# 12_SAVEFLAGS.net
KiCad netlist of a schematic drawn in EAGLE
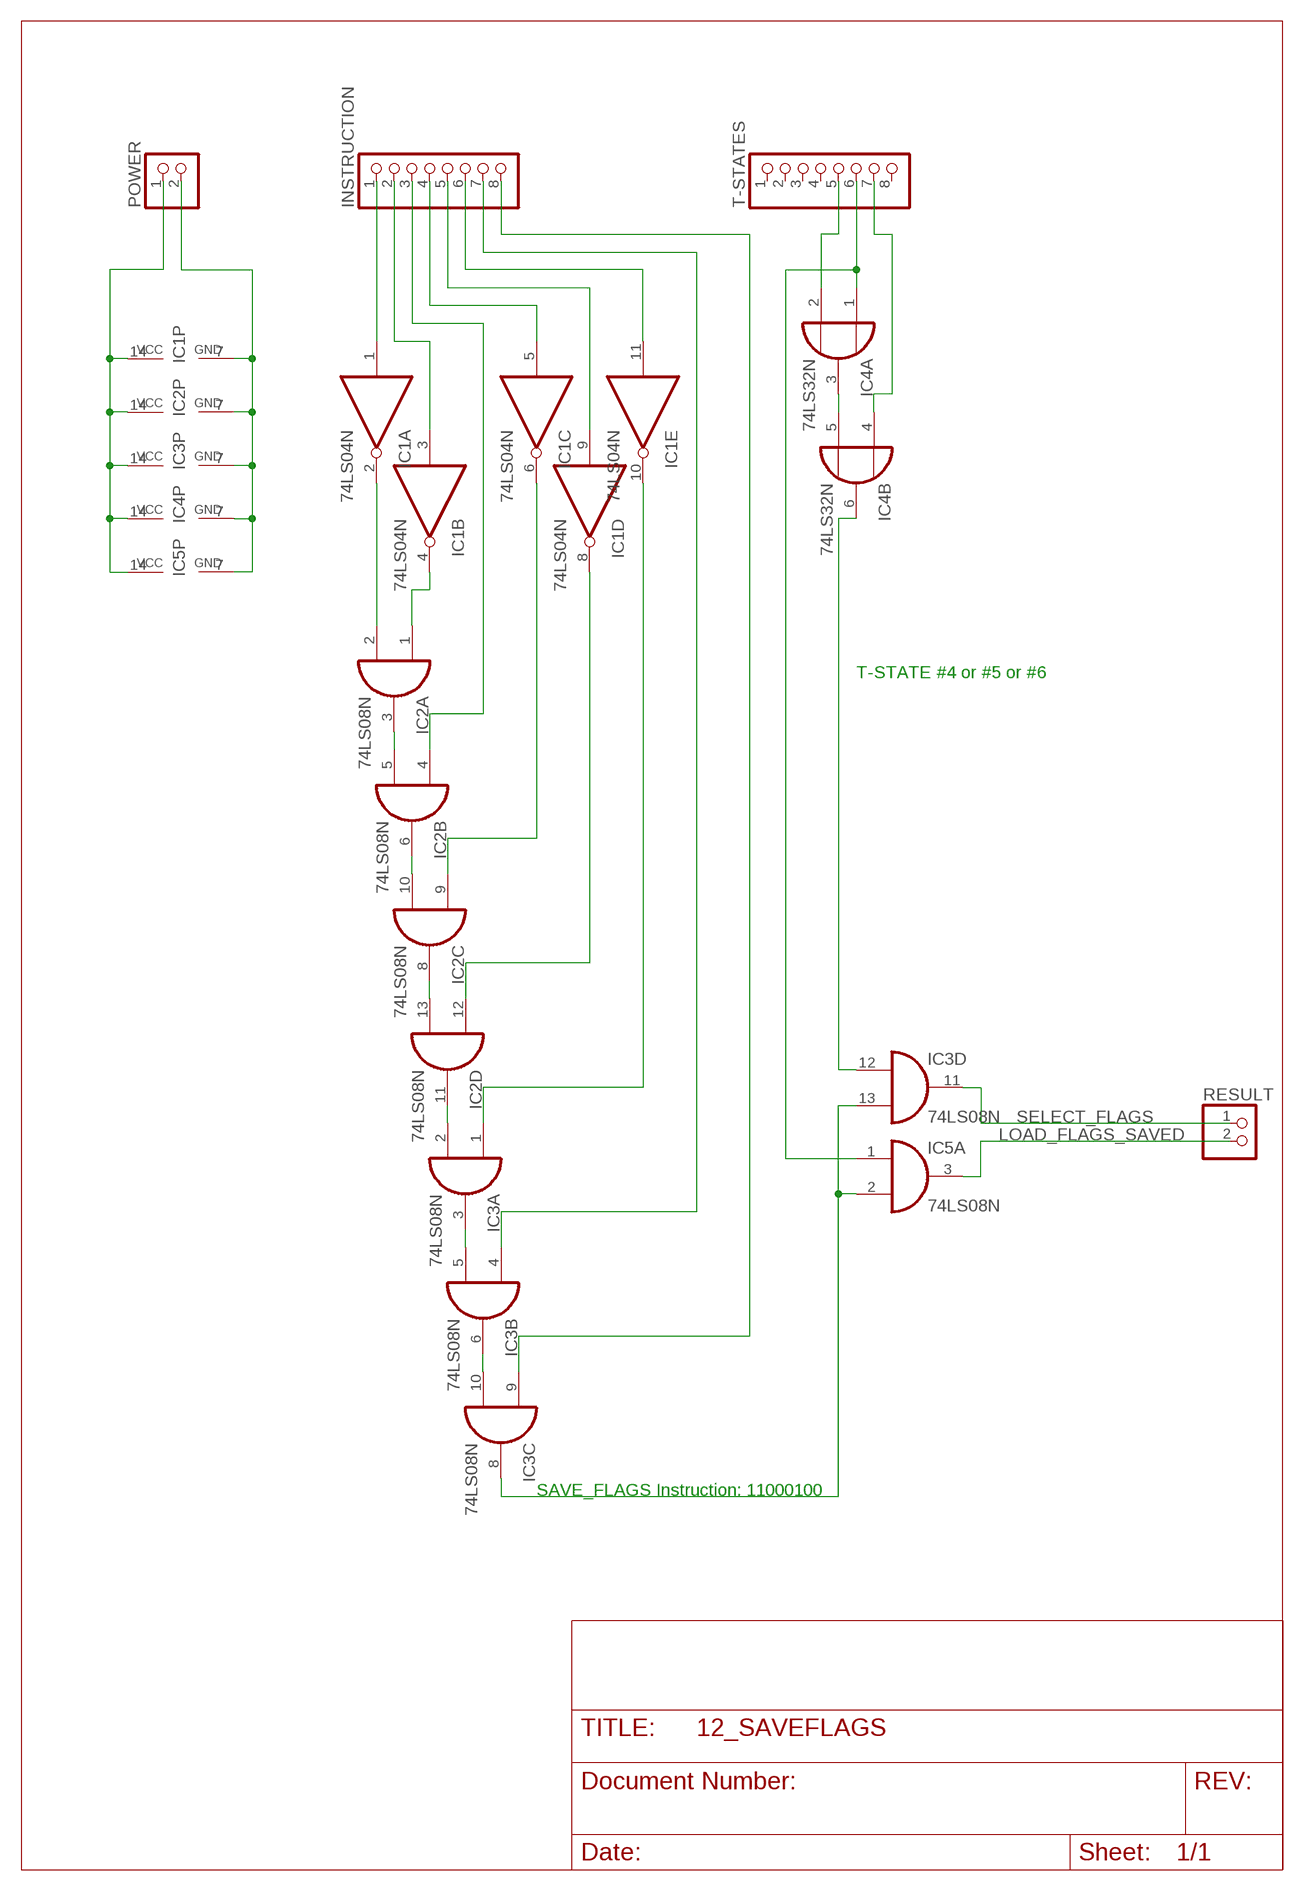
[diagram p0: schematic, sheet 1]

(export (version "E")
  (design (tool "Eeschema 10.0.6"))
  (components
    (comp (ref "IC1")
      (value "74LS04N")
      (footprint "eagle-import:DIL14")
      (libsource (lib "eagle-import") (part "7404NLS"))
    )
    (comp (ref "IC2")
      (value "74LS08N")
      (footprint "eagle-import:DIL14")
      (libsource (lib "eagle-import") (part "7408NLS"))
    )
    (comp (ref "IC3")
      (value "74LS08N")
      (footprint "eagle-import:DIL14")
      (libsource (lib "eagle-import") (part "7408NLS"))
    )
    (comp (ref "IC4")
      (value "74LS32N")
      (footprint "eagle-import:DIL14")
      (libsource (lib "eagle-import") (part "7432NLS"))
    )
    (comp (ref "IC5")
      (value "74LS08N")
      (footprint "eagle-import:DIL14")
      (libsource (lib "eagle-import") (part "7408NLS"))
    )
    (comp (ref "INSTRUCTION")
      (value "PINHD-1X8")
      (footprint "eagle-import:1X08")
      (libsource (lib "eagle-import") (part "PINHD-1X8"))
    )
    (comp (ref "POWER")
      (value "PINHD-1X2")
      (footprint "eagle-import:1X02")
      (libsource (lib "eagle-import") (part "PINHD-1X2"))
    )
    (comp (ref "RESULT")
      (value "PINHD-1X2")
      (footprint "eagle-import:1X02")
      (libsource (lib "eagle-import") (part "PINHD-1X2"))
    )
    (comp (ref "T-STATES")
      (value "PINHD-1X8")
      (footprint "eagle-import:1X08")
      (libsource (lib "eagle-import") (part "PINHD-1X8"))
    )
  )
  (nets
    (net (code "1") (name "/LOAD_FLAGS_SAVED") (class "Default")
      (node (ref "IC5") (pin "3") (pinfunction "O_3") (pintype "output"))
      (node (ref "RESULT") (pin "2") (pinfunction "2_2") (pintype "passive"))
    )
    (net (code "2") (name "/SELECT_FLAGS") (class "Default")
      (node (ref "IC3") (pin "11") (pinfunction "O_11") (pintype "output"))
      (node (ref "RESULT") (pin "1") (pinfunction "1_1") (pintype "passive"))
    )
    (net (code "3") (name "Net-(IC1A-I)") (class "Default")
      (node (ref "IC1") (pin "1") (pinfunction "I_1") (pintype "input"))
      (node (ref "INSTRUCTION") (pin "1") (pinfunction "1_1") (pintype "passive"))
    )
    (net (code "4") (name "Net-(IC1A-O)") (class "Default")
      (node (ref "IC1") (pin "2") (pinfunction "O_2") (pintype "output"))
      (node (ref "IC2") (pin "2") (pinfunction "I1_2") (pintype "input"))
    )
    (net (code "5") (name "Net-(IC1B-I)") (class "Default")
      (node (ref "IC1") (pin "3") (pinfunction "I_3") (pintype "input"))
      (node (ref "INSTRUCTION") (pin "2") (pinfunction "2_2") (pintype "passive"))
    )
    (net (code "6") (name "Net-(IC1B-O)") (class "Default")
      (node (ref "IC1") (pin "4") (pinfunction "O_4") (pintype "output"))
      (node (ref "IC2") (pin "1") (pinfunction "I0_1") (pintype "input"))
    )
    (net (code "7") (name "Net-(IC1C-I)") (class "Default")
      (node (ref "IC1") (pin "5") (pinfunction "I_5") (pintype "input"))
      (node (ref "INSTRUCTION") (pin "4") (pinfunction "4_4") (pintype "passive"))
    )
    (net (code "8") (name "Net-(IC1C-O)") (class "Default")
      (node (ref "IC1") (pin "6") (pinfunction "O_6") (pintype "output"))
      (node (ref "IC2") (pin "9") (pinfunction "I0_9") (pintype "input"))
    )
    (net (code "9") (name "Net-(IC1D-I)") (class "Default")
      (node (ref "IC1") (pin "9") (pinfunction "I_9") (pintype "input"))
      (node (ref "INSTRUCTION") (pin "5") (pinfunction "5_5") (pintype "passive"))
    )
    (net (code "10") (name "Net-(IC1D-O)") (class "Default")
      (node (ref "IC1") (pin "8") (pinfunction "O_8") (pintype "output"))
      (node (ref "IC2") (pin "12") (pinfunction "I0_12") (pintype "input"))
    )
    (net (code "11") (name "Net-(IC1E-I)") (class "Default")
      (node (ref "IC1") (pin "11") (pinfunction "I_11") (pintype "input"))
      (node (ref "INSTRUCTION") (pin "6") (pinfunction "6_6") (pintype "passive"))
    )
    (net (code "12") (name "Net-(IC1E-O)") (class "Default")
      (node (ref "IC1") (pin "10") (pinfunction "O_10") (pintype "output"))
      (node (ref "IC3") (pin "1") (pinfunction "I0_1") (pintype "input"))
    )
    (net (code "13") (name "Net-(IC1G-GND)") (class "Default")
      (node (ref "IC1") (pin "7") (pinfunction "GND_7") (pintype "power_in"))
      (node (ref "IC2") (pin "7") (pinfunction "GND_7") (pintype "power_in"))
      (node (ref "IC3") (pin "7") (pinfunction "GND_7") (pintype "power_in"))
      (node (ref "IC4") (pin "7") (pinfunction "GND_7") (pintype "power_in"))
      (node (ref "IC5") (pin "7") (pinfunction "GND_7") (pintype "power_in"))
      (node (ref "POWER") (pin "2") (pinfunction "2_2") (pintype "passive"))
    )
    (net (code "14") (name "Net-(IC1G-VCC)") (class "Default")
      (node (ref "IC1") (pin "14") (pinfunction "VCC_14") (pintype "power_in"))
      (node (ref "IC2") (pin "14") (pinfunction "VCC_14") (pintype "power_in"))
      (node (ref "IC3") (pin "14") (pinfunction "VCC_14") (pintype "power_in"))
      (node (ref "IC4") (pin "14") (pinfunction "VCC_14") (pintype "power_in"))
      (node (ref "IC5") (pin "14") (pinfunction "VCC_14") (pintype "power_in"))
      (node (ref "POWER") (pin "1") (pinfunction "1_1") (pintype "passive"))
    )
    (net (code "15") (name "Net-(IC2A-O)") (class "Default")
      (node (ref "IC2") (pin "3") (pinfunction "O_3") (pintype "output"))
      (node (ref "IC2") (pin "5") (pinfunction "I1_5") (pintype "input"))
    )
    (net (code "16") (name "Net-(IC2B-I0)") (class "Default")
      (node (ref "IC2") (pin "4") (pinfunction "I0_4") (pintype "input"))
      (node (ref "INSTRUCTION") (pin "3") (pinfunction "3_3") (pintype "passive"))
    )
    (net (code "17") (name "Net-(IC2B-O)") (class "Default")
      (node (ref "IC2") (pin "10") (pinfunction "I1_10") (pintype "input"))
      (node (ref "IC2") (pin "6") (pinfunction "O_6") (pintype "output"))
    )
    (net (code "18") (name "Net-(IC2C-O)") (class "Default")
      (node (ref "IC2") (pin "13") (pinfunction "I1_13") (pintype "input"))
      (node (ref "IC2") (pin "8") (pinfunction "O_8") (pintype "output"))
    )
    (net (code "19") (name "Net-(IC2D-O)") (class "Default")
      (node (ref "IC2") (pin "11") (pinfunction "O_11") (pintype "output"))
      (node (ref "IC3") (pin "2") (pinfunction "I1_2") (pintype "input"))
    )
    (net (code "20") (name "Net-(IC3A-O)") (class "Default")
      (node (ref "IC3") (pin "3") (pinfunction "O_3") (pintype "output"))
      (node (ref "IC3") (pin "5") (pinfunction "I1_5") (pintype "input"))
    )
    (net (code "21") (name "Net-(IC3B-I0)") (class "Default")
      (node (ref "IC3") (pin "4") (pinfunction "I0_4") (pintype "input"))
      (node (ref "INSTRUCTION") (pin "7") (pinfunction "7_7") (pintype "passive"))
    )
    (net (code "22") (name "Net-(IC3B-O)") (class "Default")
      (node (ref "IC3") (pin "10") (pinfunction "I1_10") (pintype "input"))
      (node (ref "IC3") (pin "6") (pinfunction "O_6") (pintype "output"))
    )
    (net (code "23") (name "Net-(IC3C-I0)") (class "Default")
      (node (ref "IC3") (pin "9") (pinfunction "I0_9") (pintype "input"))
      (node (ref "INSTRUCTION") (pin "8") (pinfunction "8_8") (pintype "passive"))
    )
    (net (code "24") (name "Net-(IC3C-O)") (class "Default")
      (node (ref "IC3") (pin "13") (pinfunction "I1_13") (pintype "input"))
      (node (ref "IC3") (pin "8") (pinfunction "O_8") (pintype "output"))
      (node (ref "IC5") (pin "2") (pinfunction "I1_2") (pintype "input"))
    )
    (net (code "25") (name "Net-(IC3D-I0)") (class "Default")
      (node (ref "IC3") (pin "12") (pinfunction "I0_12") (pintype "input"))
      (node (ref "IC4") (pin "6") (pinfunction "O_6") (pintype "output"))
    )
    (net (code "26") (name "Net-(IC4A-I0)") (class "Default")
      (node (ref "IC4") (pin "1") (pinfunction "I0_1") (pintype "input"))
      (node (ref "IC5") (pin "1") (pinfunction "I0_1") (pintype "input"))
      (node (ref "T-STATES") (pin "6") (pinfunction "6_6") (pintype "passive"))
    )
    (net (code "27") (name "Net-(IC4A-I1)") (class "Default")
      (node (ref "IC4") (pin "2") (pinfunction "I1_2") (pintype "input"))
      (node (ref "T-STATES") (pin "5") (pinfunction "5_5") (pintype "passive"))
    )
    (net (code "28") (name "Net-(IC4A-O)") (class "Default")
      (node (ref "IC4") (pin "3") (pinfunction "O_3") (pintype "output"))
      (node (ref "IC4") (pin "5") (pinfunction "I1_5") (pintype "input"))
    )
    (net (code "29") (name "Net-(IC4B-I0)") (class "Default")
      (node (ref "IC4") (pin "4") (pinfunction "I0_4") (pintype "input"))
      (node (ref "T-STATES") (pin "7") (pinfunction "7_7") (pintype "passive"))
    )
    (net (code "30") (name "unconnected-(T-STATES-Pad1)") (class "Default")
      (node (ref "T-STATES") (pin "1") (pinfunction "1_1") (pintype "passive"))
    )
    (net (code "31") (name "unconnected-(T-STATES-Pad2)") (class "Default")
      (node (ref "T-STATES") (pin "2") (pinfunction "2_2") (pintype "passive"))
    )
    (net (code "32") (name "unconnected-(T-STATES-Pad3)") (class "Default")
      (node (ref "T-STATES") (pin "3") (pinfunction "3_3") (pintype "passive"))
    )
    (net (code "33") (name "unconnected-(T-STATES-Pad4)") (class "Default")
      (node (ref "T-STATES") (pin "4") (pinfunction "4_4") (pintype "passive"))
    )
    (net (code "34") (name "unconnected-(T-STATES-Pad8)") (class "Default")
      (node (ref "T-STATES") (pin "8") (pinfunction "8_8") (pintype "passive"))
    )
  )
)
